# Sheet2.net
KiCad netlist of a schematic drawn in Altium Designer
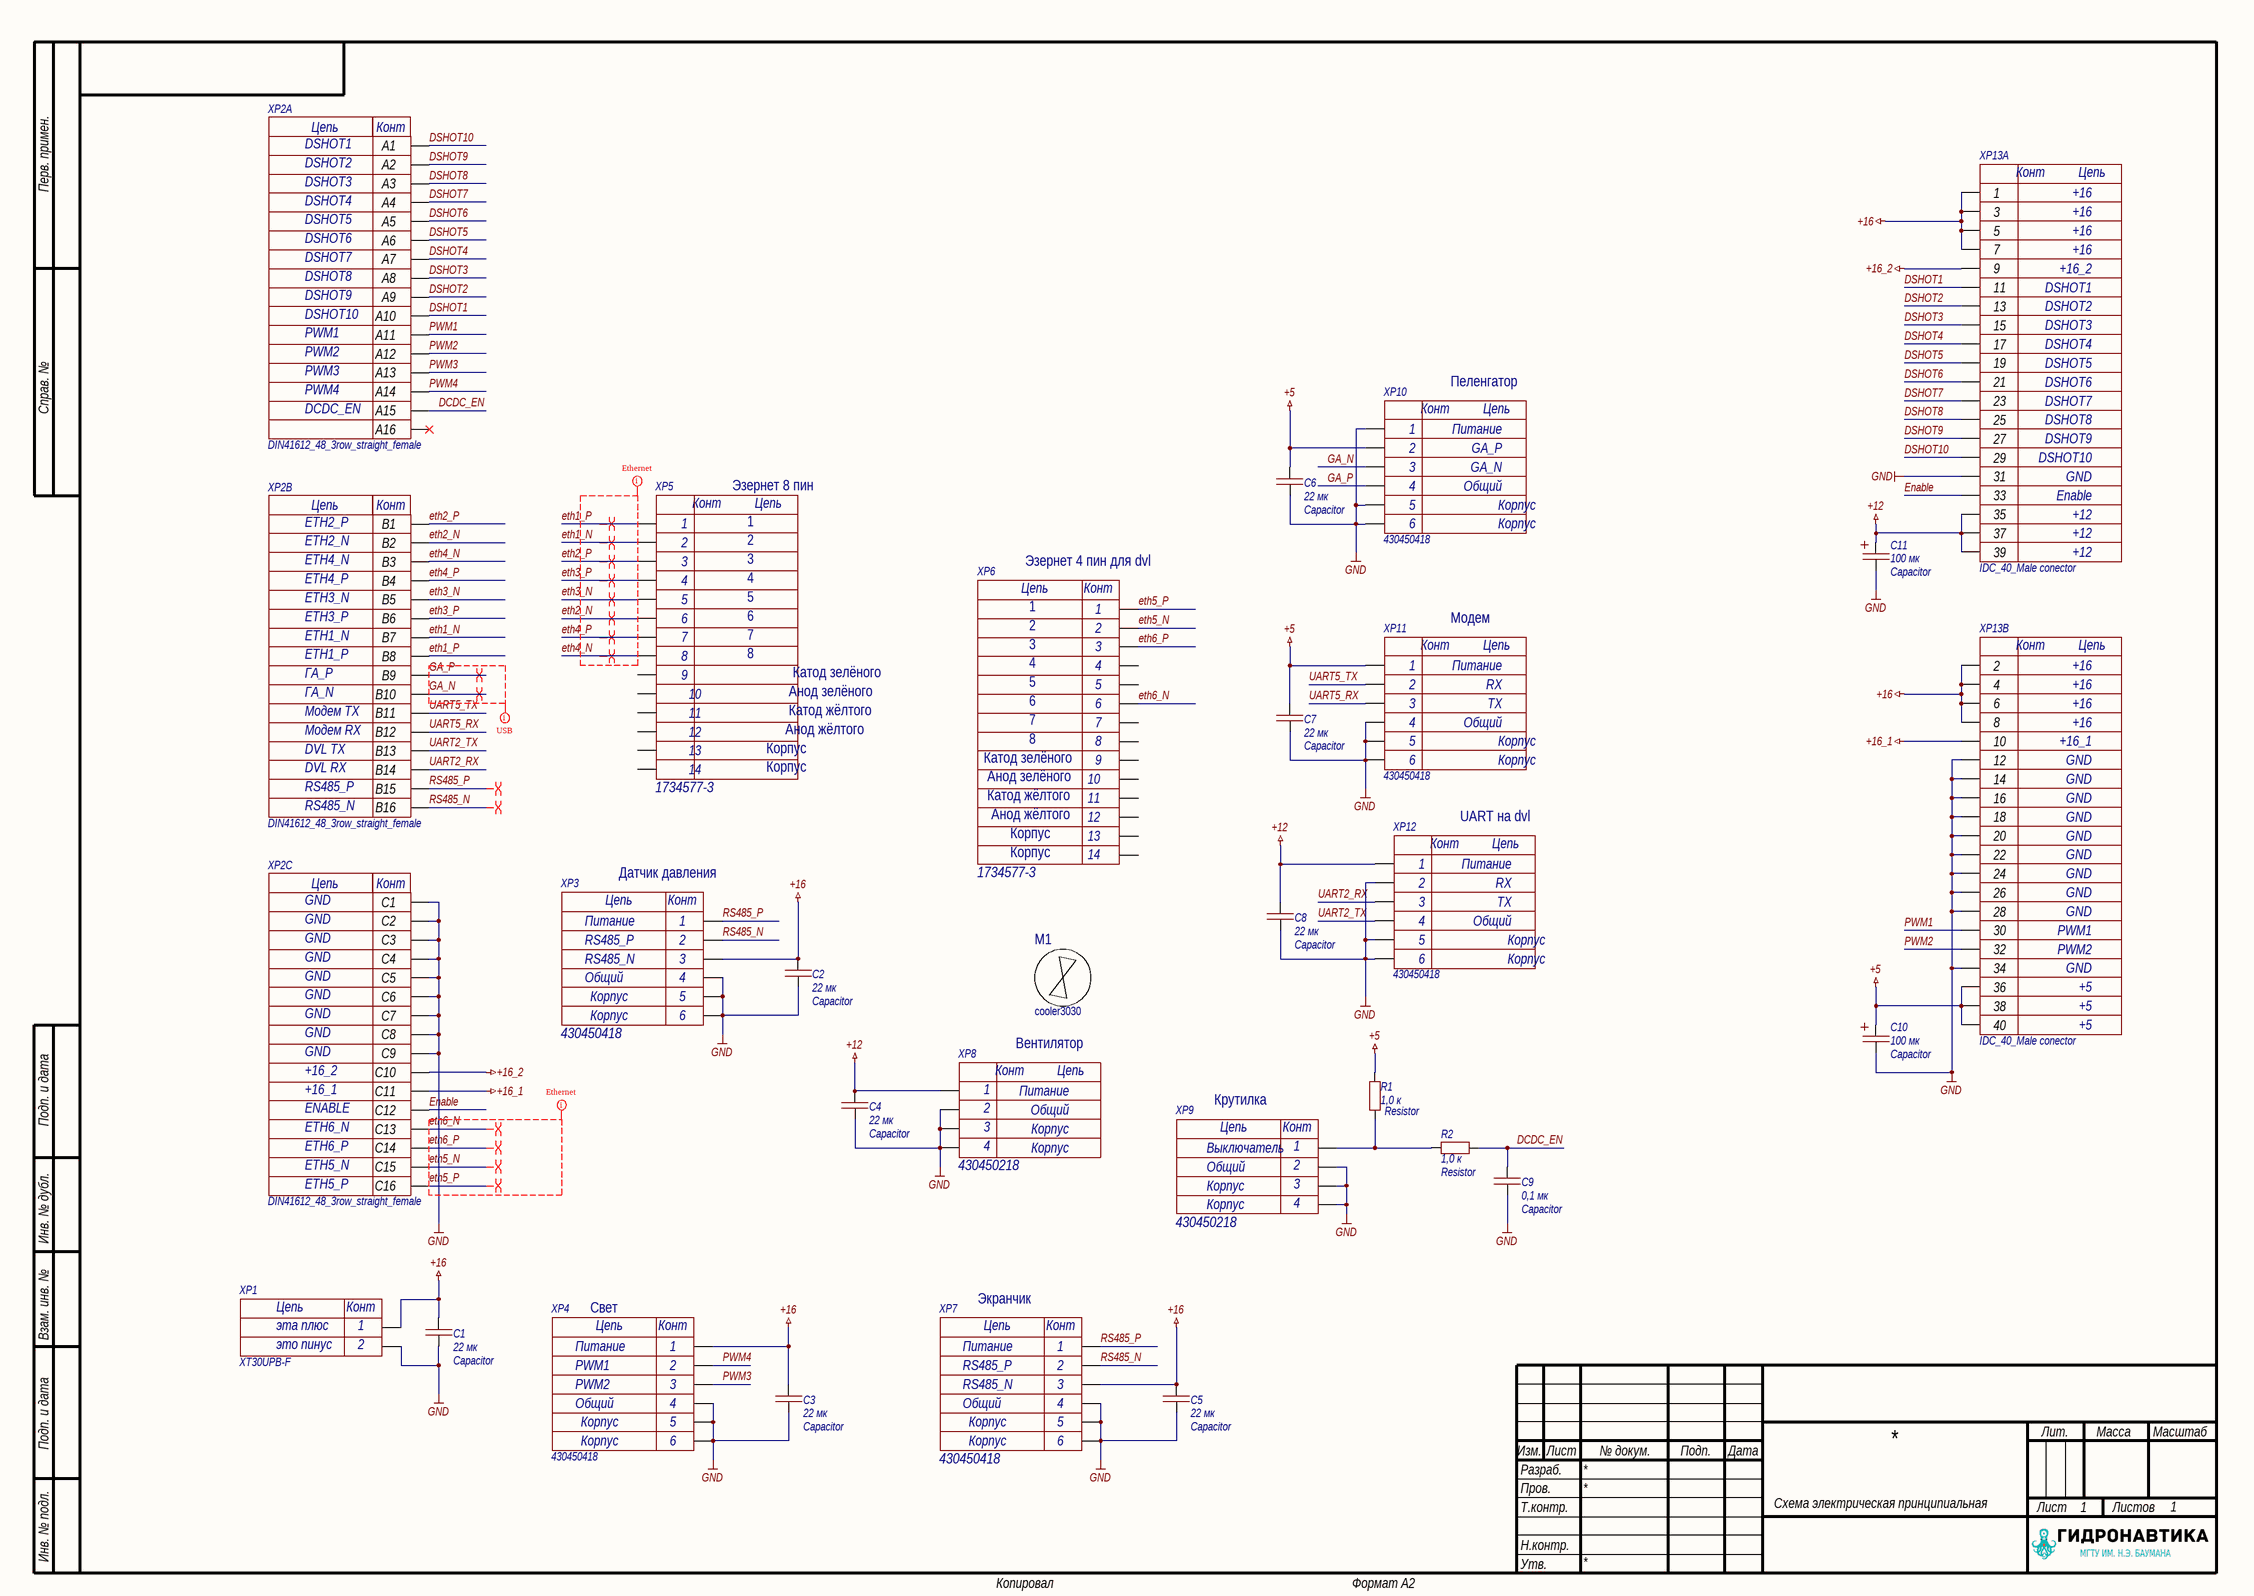
[diagram p0: Sheet2.SchDoc]

(export (version "E")
  (design (tool "Eeschema 10.0.6"))
  (components
    (comp (ref "C1")
      (value "Capacitor")
      (footprint "1210C")
      (description "Конденсатор 1210C ёмкостью 22 мк 10%, 25 В, X7R")
      (fields
        (field (name "ALTIUM_VALUE") "22 мк")
        (field (name "PART NUMBER") "Capacitor_22u_10_25V_X7R_1210C")
        (field (name "TOLERANCE") "10%")
      )
      (libsource (lib "Hydrolib") (part "Capacitor"))
    )
    (comp (ref "C2")
      (value "Capacitor")
      (footprint "1210C")
      (description "Конденсатор 1210C ёмкостью 22 мк 10%, 25 В, X7R")
      (fields
        (field (name "ALTIUM_VALUE") "22 мк")
        (field (name "PART NUMBER") "Capacitor_22u_10_25V_X7R_1210C")
        (field (name "TOLERANCE") "10%")
      )
      (libsource (lib "Hydrolib") (part "Capacitor"))
    )
    (comp (ref "C3")
      (value "Capacitor")
      (footprint "1210C")
      (description "Конденсатор 1210C ёмкостью 22 мк 10%, 25 В, X7R")
      (fields
        (field (name "ALTIUM_VALUE") "22 мк")
        (field (name "PART NUMBER") "Capacitor_22u_10_25V_X7R_1210C")
        (field (name "TOLERANCE") "10%")
      )
      (libsource (lib "Hydrolib") (part "Capacitor"))
    )
    (comp (ref "C4")
      (value "Capacitor")
      (footprint "1210C")
      (description "Конденсатор 1210C ёмкостью 22 мк 10%, 25 В, X7R")
      (fields
        (field (name "ALTIUM_VALUE") "22 мк")
        (field (name "PART NUMBER") "Capacitor_22u_10_25V_X7R_1210C")
        (field (name "TOLERANCE") "10%")
      )
      (libsource (lib "Hydrolib") (part "Capacitor"))
    )
    (comp (ref "C5")
      (value "Capacitor")
      (footprint "1210C")
      (description "Конденсатор 1210C ёмкостью 22 мк 10%, 25 В, X7R")
      (fields
        (field (name "ALTIUM_VALUE") "22 мк")
        (field (name "PART NUMBER") "Capacitor_22u_10_25V_X7R_1210C")
        (field (name "TOLERANCE") "10%")
      )
      (libsource (lib "Hydrolib") (part "Capacitor"))
    )
    (comp (ref "C6")
      (value "Capacitor")
      (footprint "1210C")
      (description "Конденсатор 1210C ёмкостью 22 мк 10%, 25 В, X7R")
      (fields
        (field (name "ALTIUM_VALUE") "22 мк")
        (field (name "PART NUMBER") "Capacitor_22u_10_25V_X7R_1210C")
        (field (name "TOLERANCE") "10%")
      )
      (libsource (lib "Hydrolib") (part "Capacitor"))
    )
    (comp (ref "C7")
      (value "Capacitor")
      (footprint "1210C")
      (description "Конденсатор 1210C ёмкостью 22 мк 10%, 25 В, X7R")
      (fields
        (field (name "ALTIUM_VALUE") "22 мк")
        (field (name "PART NUMBER") "Capacitor_22u_10_25V_X7R_1210C")
        (field (name "TOLERANCE") "10%")
      )
      (libsource (lib "Hydrolib") (part "Capacitor"))
    )
    (comp (ref "C8")
      (value "Capacitor")
      (footprint "1210C")
      (description "Конденсатор 1210C ёмкостью 22 мк 10%, 25 В, X7R")
      (fields
        (field (name "ALTIUM_VALUE") "22 мк")
        (field (name "PART NUMBER") "Capacitor_22u_10_25V_X7R_1210C")
        (field (name "TOLERANCE") "10%")
      )
      (libsource (lib "Hydrolib") (part "Capacitor"))
    )
    (comp (ref "C9")
      (value "Capacitor")
      (footprint "0603C")
      (description "Конденсатор 0603C ёмкостью 0,1 мк 10%, 50 В, X7R")
      (fields
        (field (name "ALTIUM_VALUE") "0,1 мк")
        (field (name "PART NUMBER") "Capacitor_0,1u_10_50V_X7R_0603C")
        (field (name "TOLERANCE") "10%")
      )
      (libsource (lib "Hydrolib") (part "Capacitor"))
    )
    (comp (ref "C10")
      (value "Capacitor")
      (footprint "ECAP_SMD_6,6x6,6")
      (description "Конденсатор алюминиевый электролитический 100мкФ 35В 20% SMD 6,6x6,6 мм")
      (fields
        (field (name "ALTIUM_VALUE") "100 мк")
        (field (name "PART NUMBER") "JCK1V101")
        (field (name "TOLERANCE") "20")
      )
      (libsource (lib "Hydrolib") (part "Capacitor_polar"))
    )
    (comp (ref "C11")
      (value "Capacitor")
      (footprint "ECAP_SMD_6,6x6,6")
      (description "Конденсатор алюминиевый электролитический 100мкФ 35В 20% SMD 6,6x6,6 мм")
      (fields
        (field (name "ALTIUM_VALUE") "100 мк")
        (field (name "PART NUMBER") "JCK1V101")
        (field (name "TOLERANCE") "20")
      )
      (libsource (lib "Hydrolib") (part "Capacitor_polar"))
    )
    (comp (ref "M1")
      (value "cooler3030")
      (footprint "cooler3030")
      (description "вентилятор 30*30 с дыркой на плате")
      (libsource (lib "Hydrolib") (part "cooler4040"))
    )
    (comp (ref "R1")
      (value "Resistor")
      (footprint "0603R")
      (description "Резистор номиналом 1,0 кОм 1%")
      (fields
        (field (name "ALTIUM_VALUE") "1,0 к")
        (field (name "PART NUMBER") "Resistor_1.0k_1_0603")
        (field (name "TOLERANCE") "1%")
      )
      (libsource (lib "") (part "Resistor_1"))
    )
    (comp (ref "R2")
      (value "Resistor")
      (footprint "0603R")
      (description "Резистор номиналом 1,0 кОм 1%")
      (fields
        (field (name "ALTIUM_VALUE") "1,0 к")
        (field (name "PART NUMBER") "Resistor_1.0k_1_0603")
        (field (name "TOLERANCE") "1%")
      )
      (libsource (lib "Hydrolib") (part "Resistor"))
    )
    (comp (ref "XP1")
      (value "XT30UPB-F")
      (footprint "XT30UPB-F")
      (description "30 А (15 продолжительно), прямая мать")
      (fields (field (name "VALUE2") "это пинус") (field (name "VALUE1") "эта плюс"))
      (libsource (lib "Hydrolib") (part "Polar_Conn"))
    )
    (comp (ref "XP2")
      (value "DIN41612_48_3row_straight_female")
      (footprint "DIN41612_48_3row_straight_female")
      (fields
        (field (name "PARAMETER 14") "DCDC_EN")
        (field (name "PARAMETER 16") "RS485_N")
        (field (name "PARAMETER 15") "PWM4")
        (field (name "PARAMETER 12") "DSHOT7")
        (field (name "PARAMETER 13") "DSHOT5")
        (field (name "PARAMETER 11") "DSHOT6")
        (field (name "PARAMETER 10") "DSHOT4")
        (field (name "PARAMETER 9") "DSHOT3")
        (field (name "PARAMETER 8") "DSHOT2")
        (field (name "PARAMETER 5") "DSHOT1")
        (field (name "PARAMETER 6") "PWM2")
        (field (name "PARAMETER 7") "PWM3")
        (field (name "PARAMETER 4") "DSHOT10")
        (field (name "PARAMETER 3") "DSHOT9")
        (field (name "PARAMETER 2") "DSHOT8")
        (field (name "PARAMETER 1") "PWM1")
      )
      (libsource (lib "") (part "Conn_48pin_3row_1"))
    )
    (comp (ref "XP3")
      (value "430450418")
      (footprint "MOLEX_430450418")
      (description "Разъем типа провод-плата, 3 мм, 4 контакт(-ов), Штыревой Разъем, для поверностного монтажа")
      (fields
        (field (name "VALUE1") "Питание")
        (field (name "VALUE2") "RS485_P")
        (field (name "VALUE3") "RS485_N")
        (field (name "VALUE4") "Общий")
        (field (name "PART NUMBER") "Molex_430450418")
      )
      (libsource (lib "") (part "Molex_430450415_1"))
    )
    (comp (ref "XP4")
      (value "430450418")
      (footprint "MOLEX_430450418")
      (description "Разъем типа провод-плата, 3 мм, 4 контакт(-ов), Штыревой Разъем, для поверностного монтажа")
      (fields
        (field (name "VALUE1") "Питание")
        (field (name "VALUE2") "PWM1")
        (field (name "VALUE3") "PWM2")
        (field (name "VALUE4") "Общий")
        (field (name "PART NUMBER") "Molex_430450418")
      )
      (libsource (lib "") (part "Molex_430450415_1"))
    )
    (comp (ref "XP5")
      (value "1734577-3")
      (footprint "1-1734577-3-rj45-8p8c")
      (description "Модульный разъем, Cat3, RJ45, Гнездо, 8 контакт(-ов), 8 вывод(-ов), 1 порт(-ов)")
      (fields (field (name "PART NUMBER") "1-1734577-3-rj45-8p8c"))
      (libsource (lib "Hydrolib") (part "1-1734577-3-rj45-8p8c"))
    )
    (comp (ref "XP6")
      (value "1734577-3")
      (footprint "1-1734577-3-rj45-8p8c")
      (description "Модульный разъем, Cat3, RJ45, Гнездо, 8 контакт(-ов), 8 вывод(-ов), 1 порт(-ов)")
      (fields (field (name "PART NUMBER") "1-1734577-3-rj45-8p8c"))
      (libsource (lib "") (part "1-1734577-3-rj45-8p8c_1"))
    )
    (comp (ref "XP7")
      (value "430450418")
      (footprint "MOLEX_430450418")
      (description "Разъем типа провод-плата, 3 мм, 4 контакт(-ов), Штыревой Разъем, для поверностного монтажа")
      (fields
        (field (name "VALUE1") "Питание")
        (field (name "VALUE2") "RS485_P")
        (field (name "VALUE3") "RS485_N")
        (field (name "VALUE4") "Общий")
        (field (name "PART NUMBER") "Molex_430450418")
      )
      (libsource (lib "") (part "Molex_430450415_1"))
    )
    (comp (ref "XP8")
      (value "430450218")
      (footprint "Molex_430450218")
      (fields
        (field (name "VALUE3") "Корпус")
        (field (name "VALUE2") "Общий")
        (field (name "VALUE4") "Корпус")
        (field (name "VALUE1") "Питание")
        (field (name "PART NUMBER") "Molex_430450218")
      )
      (libsource (lib "Hydrolib") (part "Molex_430450218"))
    )
    (comp (ref "XP9")
      (value "430450218")
      (footprint "Molex_430450218")
      (fields
        (field (name "VALUE3") "Корпус")
        (field (name "VALUE2") "Общий")
        (field (name "VALUE4") "Корпус")
        (field (name "VALUE1") "Выключатель")
        (field (name "PART NUMBER") "Molex_430450218")
      )
      (libsource (lib "Hydrolib") (part "Molex_430450218"))
    )
    (comp (ref "XP10")
      (value "430450418")
      (footprint "MOLEX_430450418")
      (description "Разъем типа провод-плата, 3 мм, 4 контакт(-ов), Штыревой Разъем, для поверностного монтажа")
      (fields
        (field (name "VALUE1") "Питание")
        (field (name "VALUE2") "GA_P")
        (field (name "VALUE3") "GA_N")
        (field (name "VALUE4") "Общий")
        (field (name "PART NUMBER") "Molex_430450418")
      )
      (libsource (lib "Hydrolib") (part "Molex_430450415"))
    )
    (comp (ref "XP11")
      (value "430450418")
      (footprint "MOLEX_430450418")
      (description "Разъем типа провод-плата, 3 мм, 4 контакт(-ов), Штыревой Разъем, для поверностного монтажа")
      (fields
        (field (name "VALUE1") "Питание")
        (field (name "VALUE2") "RX")
        (field (name "VALUE3") "TX")
        (field (name "VALUE4") "Общий")
        (field (name "PART NUMBER") "Molex_430450418")
      )
      (libsource (lib "Hydrolib") (part "Molex_430450415"))
    )
    (comp (ref "XP12")
      (value "430450418")
      (footprint "MOLEX_430450418")
      (description "Разъем типа провод-плата, 3 мм, 4 контакт(-ов), Штыревой Разъем, для поверностного монтажа")
      (fields
        (field (name "VALUE1") "Питание")
        (field (name "VALUE2") "RX")
        (field (name "VALUE3") "TX")
        (field (name "VALUE4") "Общий")
        (field (name "PART NUMBER") "Molex_430450418")
      )
      (libsource (lib "Hydrolib") (part "Molex_430450415"))
    )
    (comp (ref "XP13")
      (value "IDC_40_Male conector")
      (footprint "IDC_40_Male conector")
      (description "IDC 40-пиновый разъём прямая вилка")
      (fields
        (field (name "VALUE17") "GND")
        (field (name "VALUE20") "+5")
        (field (name "VALUE19") "+5")
        (field (name "VALUE18") "+5")
        (field (name "VALUE16") "PWM2")
        (field (name "VALUE15") "PWM1")
        (field (name "VALUE14") "GND")
        (field (name "VALUE13") "GND")
        (field (name "VALUE12") "GND")
        (field (name "VALUE11") "GND")
        (field (name "VALUE10") "GND")
        (field (name "VALUE9") "GND")
        (field (name "VALUE8") "GND")
        (field (name "VALUE7") "GND")
        (field (name "VALUE6") "GND")
        (field (name "VALUE5") "+16_1")
        (field (name "VALUE4") "+16")
        (field (name "VALUE3") "+16")
        (field (name "VALUE2") "+16")
        (field (name "VALUE1") "+16")
      )
      (libsource (lib "Hydrolib") (part "Conn_40pin_double"))
    )
  )
  (nets
    (net (code "1") (name "+5") (class "Default")
      (node (ref "C10") (pin "1") (pinfunction "1_1") (pintype "passive"))
      (node (ref "C6") (pin "2") (pinfunction "2_2") (pintype "passive"))
      (node (ref "C7") (pin "2") (pinfunction "2_2") (pintype "passive"))
      (node (ref "R1") (pin "1") (pinfunction "1_1") (pintype "passive"))
      (node (ref "XP10") (pin "2") (pinfunction "2_2") (pintype "passive"))
      (node (ref "XP11") (pin "1") (pinfunction "1_1") (pintype "passive"))
      (node (ref "XP13") (pin "36") (pinfunction "36_36") (pintype "passive"))
      (node (ref "XP13") (pin "38") (pinfunction "38_38") (pintype "passive"))
      (node (ref "XP13") (pin "40") (pinfunction "40_40") (pintype "passive"))
    )
    (net (code "2") (name "+12") (class "Default")
      (node (ref "C11") (pin "1") (pinfunction "1_1") (pintype "passive"))
      (node (ref "C4") (pin "2") (pinfunction "2_2") (pintype "passive"))
      (node (ref "C8") (pin "2") (pinfunction "2_2") (pintype "passive"))
      (node (ref "XP12") (pin "1") (pinfunction "1_1") (pintype "passive"))
      (node (ref "XP13") (pin "35") (pinfunction "35_35") (pintype "passive"))
      (node (ref "XP13") (pin "37") (pinfunction "37_37") (pintype "passive"))
      (node (ref "XP13") (pin "39") (pinfunction "39_39") (pintype "passive"))
      (node (ref "XP8") (pin "1") (pinfunction "1_1") (pintype "passive"))
    )
    (net (code "3") (name "+16") (class "Default")
      (node (ref "C1") (pin "2") (pinfunction "2_2") (pintype "passive"))
      (node (ref "C2") (pin "2") (pinfunction "2_2") (pintype "passive"))
      (node (ref "C3") (pin "2") (pinfunction "2_2") (pintype "passive"))
      (node (ref "C5") (pin "2") (pinfunction "2_2") (pintype "passive"))
      (node (ref "XP1") (pin "P") (pinfunction "P_P") (pintype "passive"))
      (node (ref "XP13") (pin "1") (pinfunction "1_1") (pintype "passive"))
      (node (ref "XP13") (pin "2") (pinfunction "2_2") (pintype "passive"))
      (node (ref "XP13") (pin "3") (pinfunction "3_3") (pintype "passive"))
      (node (ref "XP13") (pin "4") (pinfunction "4_4") (pintype "passive"))
      (node (ref "XP13") (pin "5") (pinfunction "5_5") (pintype "passive"))
      (node (ref "XP13") (pin "6") (pinfunction "6_6") (pintype "passive"))
      (node (ref "XP13") (pin "7") (pinfunction "7_7") (pintype "passive"))
      (node (ref "XP13") (pin "8") (pinfunction "8_8") (pintype "passive"))
      (node (ref "XP3") (pin "3") (pinfunction "3_3") (pintype "passive"))
      (node (ref "XP4") (pin "1") (pinfunction "1_1") (pintype "passive"))
      (node (ref "XP7") (pin "3") (pinfunction "3_3") (pintype "passive"))
    )
    (net (code "4") (name "+16_1") (class "Default")
      (node (ref "XP13") (pin "10") (pinfunction "10_10") (pintype "passive"))
      (node (ref "XP2") (pin "C11") (pinfunction "C11_C11") (pintype "passive"))
    )
    (net (code "5") (name "+16_2") (class "Default")
      (node (ref "XP13") (pin "9") (pinfunction "9_9") (pintype "passive"))
      (node (ref "XP2") (pin "C10") (pinfunction "C10_C10") (pintype "passive"))
    )
    (net (code "6") (name "/DCDC_EN") (class "Default")
      (node (ref "C9") (pin "2") (pinfunction "2_2") (pintype "passive"))
      (node (ref "R2") (pin "1") (pinfunction "1_1") (pintype "passive"))
      (node (ref "XP2") (pin "A15") (pinfunction "A15_A15") (pintype "passive"))
    )
    (net (code "7") (name "/DSHOT1") (class "Default")
      (node (ref "XP13") (pin "11") (pinfunction "11_11") (pintype "passive"))
      (node (ref "XP2") (pin "A10") (pinfunction "A10_A10") (pintype "passive"))
    )
    (net (code "8") (name "/DSHOT2") (class "Default")
      (node (ref "XP13") (pin "13") (pinfunction "13_13") (pintype "passive"))
      (node (ref "XP2") (pin "A9") (pinfunction "A9_A9") (pintype "passive"))
    )
    (net (code "9") (name "/DSHOT3") (class "Default")
      (node (ref "XP13") (pin "15") (pinfunction "15_15") (pintype "passive"))
      (node (ref "XP2") (pin "A8") (pinfunction "A8_A8") (pintype "passive"))
    )
    (net (code "10") (name "/DSHOT4") (class "Default")
      (node (ref "XP13") (pin "17") (pinfunction "17_17") (pintype "passive"))
      (node (ref "XP2") (pin "A7") (pinfunction "A7_A7") (pintype "passive"))
    )
    (net (code "11") (name "/DSHOT5") (class "Default")
      (node (ref "XP13") (pin "19") (pinfunction "19_19") (pintype "passive"))
      (node (ref "XP2") (pin "A6") (pinfunction "A6_A6") (pintype "passive"))
    )
    (net (code "12") (name "/DSHOT6") (class "Default")
      (node (ref "XP13") (pin "21") (pinfunction "21_21") (pintype "passive"))
      (node (ref "XP2") (pin "A5") (pinfunction "A5_A5") (pintype "passive"))
    )
    (net (code "13") (name "/DSHOT7") (class "Default")
      (node (ref "XP13") (pin "23") (pinfunction "23_23") (pintype "passive"))
      (node (ref "XP2") (pin "A4") (pinfunction "A4_A4") (pintype "passive"))
    )
    (net (code "14") (name "/DSHOT8") (class "Default")
      (node (ref "XP13") (pin "25") (pinfunction "25_25") (pintype "passive"))
      (node (ref "XP2") (pin "A3") (pinfunction "A3_A3") (pintype "passive"))
    )
    (net (code "15") (name "/DSHOT9") (class "Default")
      (node (ref "XP13") (pin "27") (pinfunction "27_27") (pintype "passive"))
      (node (ref "XP2") (pin "A2") (pinfunction "A2_A2") (pintype "passive"))
    )
    (net (code "16") (name "/DSHOT10") (class "Default")
      (node (ref "XP13") (pin "29") (pinfunction "29_29") (pintype "passive"))
      (node (ref "XP2") (pin "A1") (pinfunction "A1_A1") (pintype "passive"))
    )
    (net (code "17") (name "/Enable") (class "Default")
      (node (ref "XP13") (pin "33") (pinfunction "33_33") (pintype "passive"))
      (node (ref "XP2") (pin "C12") (pinfunction "C12_C12") (pintype "passive"))
    )
    (net (code "18") (name "/GA_N") (class "Default")
      (node (ref "XP10") (pin "3") (pinfunction "3_3") (pintype "passive"))
      (node (ref "XP2") (pin "B10") (pinfunction "B10_B10") (pintype "passive"))
    )
    (net (code "19") (name "/GA_P") (class "Default")
      (node (ref "XP10") (pin "4") (pinfunction "4_4") (pintype "passive"))
      (node (ref "XP2") (pin "B9") (pinfunction "B9_B9") (pintype "passive"))
    )
    (net (code "20") (name "/PWM1") (class "Default")
      (node (ref "XP13") (pin "30") (pinfunction "30_30") (pintype "passive"))
      (node (ref "XP2") (pin "A11") (pinfunction "A11_A11") (pintype "passive"))
    )
    (net (code "21") (name "/PWM2") (class "Default")
      (node (ref "XP13") (pin "32") (pinfunction "32_32") (pintype "passive"))
      (node (ref "XP2") (pin "A12") (pinfunction "A12_A12") (pintype "passive"))
    )
    (net (code "22") (name "/PWM3") (class "Default")
      (node (ref "XP2") (pin "A13") (pinfunction "A13_A13") (pintype "passive"))
      (node (ref "XP4") (pin "3") (pinfunction "3_3") (pintype "passive"))
    )
    (net (code "23") (name "/PWM4") (class "Default")
      (node (ref "XP2") (pin "A14") (pinfunction "A14_A14") (pintype "passive"))
      (node (ref "XP4") (pin "2") (pinfunction "2_2") (pintype "passive"))
    )
    (net (code "24") (name "/RS485_N") (class "Default")
      (node (ref "XP2") (pin "B16") (pinfunction "B16_B16") (pintype "passive"))
      (node (ref "XP3") (pin "2") (pinfunction "2_2") (pintype "passive"))
      (node (ref "XP7") (pin "2") (pinfunction "2_2") (pintype "passive"))
    )
    (net (code "25") (name "/RS485_P") (class "Default")
      (node (ref "XP2") (pin "B15") (pinfunction "B15_B15") (pintype "passive"))
      (node (ref "XP3") (pin "1") (pinfunction "1_1") (pintype "passive"))
      (node (ref "XP7") (pin "1") (pinfunction "1_1") (pintype "passive"))
    )
    (net (code "26") (name "/UART2_RX") (class "Default")
      (node (ref "XP12") (pin "3") (pinfunction "3_3") (pintype "passive"))
      (node (ref "XP2") (pin "B14") (pinfunction "B14_B14") (pintype "passive"))
    )
    (net (code "27") (name "/UART2_TX") (class "Default")
      (node (ref "XP12") (pin "4") (pinfunction "4_4") (pintype "passive"))
      (node (ref "XP2") (pin "B13") (pinfunction "B13_B13") (pintype "passive"))
    )
    (net (code "28") (name "/UART5_RX") (class "Default")
      (node (ref "XP11") (pin "3") (pinfunction "3_3") (pintype "passive"))
      (node (ref "XP2") (pin "B12") (pinfunction "B12_B12") (pintype "passive"))
    )
    (net (code "29") (name "/UART5_TX") (class "Default")
      (node (ref "XP11") (pin "2") (pinfunction "2_2") (pintype "passive"))
      (node (ref "XP2") (pin "B11") (pinfunction "B11_B11") (pintype "passive"))
    )
    (net (code "30") (name "/eth1_N") (class "Default")
      (node (ref "XP2") (pin "B7") (pinfunction "B7_B7") (pintype "passive"))
      (node (ref "XP5") (pin "2") (pinfunction "2_2") (pintype "passive"))
    )
    (net (code "31") (name "/eth1_P") (class "Default")
      (node (ref "XP2") (pin "B8") (pinfunction "B8_B8") (pintype "passive"))
      (node (ref "XP5") (pin "1") (pinfunction "1_1") (pintype "passive"))
    )
    (net (code "32") (name "/eth2_N") (class "Default")
      (node (ref "XP2") (pin "B2") (pinfunction "B2_B2") (pintype "passive"))
      (node (ref "XP5") (pin "6") (pinfunction "6_6") (pintype "passive"))
    )
    (net (code "33") (name "/eth2_P") (class "Default")
      (node (ref "XP2") (pin "B1") (pinfunction "B1_B1") (pintype "passive"))
      (node (ref "XP5") (pin "3") (pinfunction "3_3") (pintype "passive"))
    )
    (net (code "34") (name "/eth3_N") (class "Default")
      (node (ref "XP2") (pin "B5") (pinfunction "B5_B5") (pintype "passive"))
      (node (ref "XP5") (pin "5") (pinfunction "5_5") (pintype "passive"))
    )
    (net (code "35") (name "/eth3_P") (class "Default")
      (node (ref "XP2") (pin "B6") (pinfunction "B6_B6") (pintype "passive"))
      (node (ref "XP5") (pin "4") (pinfunction "4_4") (pintype "passive"))
    )
    (net (code "36") (name "/eth4_N") (class "Default")
      (node (ref "XP2") (pin "B3") (pinfunction "B3_B3") (pintype "passive"))
      (node (ref "XP5") (pin "8") (pinfunction "8_8") (pintype "passive"))
    )
    (net (code "37") (name "/eth4_P") (class "Default")
      (node (ref "XP2") (pin "B4") (pinfunction "B4_B4") (pintype "passive"))
      (node (ref "XP5") (pin "7") (pinfunction "7_7") (pintype "passive"))
    )
    (net (code "38") (name "/eth5_N") (class "Default")
      (node (ref "XP2") (pin "C15") (pinfunction "C15_C15") (pintype "passive"))
      (node (ref "XP6") (pin "2") (pinfunction "2_2") (pintype "passive"))
    )
    (net (code "39") (name "/eth5_P") (class "Default")
      (node (ref "XP2") (pin "C16") (pinfunction "C16_C16") (pintype "passive"))
      (node (ref "XP6") (pin "1") (pinfunction "1_1") (pintype "passive"))
    )
    (net (code "40") (name "/eth6_N") (class "Default")
      (node (ref "XP2") (pin "C13") (pinfunction "C13_C13") (pintype "passive"))
      (node (ref "XP6") (pin "6") (pinfunction "6_6") (pintype "passive"))
    )
    (net (code "41") (name "/eth6_P") (class "Default")
      (node (ref "XP2") (pin "C14") (pinfunction "C14_C14") (pintype "passive"))
      (node (ref "XP6") (pin "3") (pinfunction "3_3") (pintype "passive"))
    )
    (net (code "42") (name "GND") (class "Default")
      (node (ref "C1") (pin "1") (pinfunction "1_1") (pintype "passive"))
      (node (ref "C10") (pin "2") (pinfunction "2_2") (pintype "passive"))
      (node (ref "C11") (pin "2") (pinfunction "2_2") (pintype "passive"))
      (node (ref "C2") (pin "1") (pinfunction "1_1") (pintype "passive"))
      (node (ref "C3") (pin "1") (pinfunction "1_1") (pintype "passive"))
      (node (ref "C4") (pin "1") (pinfunction "1_1") (pintype "passive"))
      (node (ref "C5") (pin "1") (pinfunction "1_1") (pintype "passive"))
      (node (ref "C6") (pin "1") (pinfunction "1_1") (pintype "passive"))
      (node (ref "C7") (pin "1") (pinfunction "1_1") (pintype "passive"))
      (node (ref "C8") (pin "1") (pinfunction "1_1") (pintype "passive"))
      (node (ref "C9") (pin "1") (pinfunction "1_1") (pintype "passive"))
      (node (ref "XP1") (pin "N") (pinfunction "N_N") (pintype "passive"))
      (node (ref "XP10") (pin "0") (pinfunction "0_0") (pintype "passive"))
      (node (ref "XP10") (pin "1") (pinfunction "1_1") (pintype "passive"))
      (node (ref "XP11") (pin "0") (pinfunction "0_0") (pintype "passive"))
      (node (ref "XP11") (pin "4") (pinfunction "4_4") (pintype "passive"))
      (node (ref "XP12") (pin "0") (pinfunction "0_0") (pintype "passive"))
      (node (ref "XP12") (pin "2") (pinfunction "2_2") (pintype "passive"))
      (node (ref "XP13") (pin "12") (pinfunction "12_12") (pintype "passive"))
      (node (ref "XP13") (pin "14") (pinfunction "14_14") (pintype "passive"))
      (node (ref "XP13") (pin "16") (pinfunction "16_16") (pintype "passive"))
      (node (ref "XP13") (pin "18") (pinfunction "18_18") (pintype "passive"))
      (node (ref "XP13") (pin "20") (pinfunction "20_20") (pintype "passive"))
      (node (ref "XP13") (pin "22") (pinfunction "22_22") (pintype "passive"))
      (node (ref "XP13") (pin "24") (pinfunction "24_24") (pintype "passive"))
      (node (ref "XP13") (pin "26") (pinfunction "26_26") (pintype "passive"))
      (node (ref "XP13") (pin "28") (pinfunction "28_28") (pintype "passive"))
      (node (ref "XP13") (pin "31") (pinfunction "31_31") (pintype "passive"))
      (node (ref "XP13") (pin "34") (pinfunction "34_34") (pintype "passive"))
      (node (ref "XP2") (pin "C1") (pinfunction "C1_C1") (pintype "passive"))
      (node (ref "XP2") (pin "C2") (pinfunction "C2_C2") (pintype "passive"))
      (node (ref "XP2") (pin "C3") (pinfunction "C3_C3") (pintype "passive"))
      (node (ref "XP2") (pin "C4") (pinfunction "C4_C4") (pintype "passive"))
      (node (ref "XP2") (pin "C5") (pinfunction "C5_C5") (pintype "passive"))
      (node (ref "XP2") (pin "C6") (pinfunction "C6_C6") (pintype "passive"))
      (node (ref "XP2") (pin "C7") (pinfunction "C7_C7") (pintype "passive"))
      (node (ref "XP2") (pin "C8") (pinfunction "C8_C8") (pintype "passive"))
      (node (ref "XP2") (pin "C9") (pinfunction "C9_C9") (pintype "passive"))
      (node (ref "XP3") (pin "0") (pinfunction "0_0") (pintype "passive"))
      (node (ref "XP3") (pin "4") (pinfunction "4_4") (pintype "passive"))
      (node (ref "XP4") (pin "0") (pinfunction "0_0") (pintype "passive"))
      (node (ref "XP4") (pin "4") (pinfunction "4_4") (pintype "passive"))
      (node (ref "XP7") (pin "0") (pinfunction "0_0") (pintype "passive"))
      (node (ref "XP7") (pin "4") (pinfunction "4_4") (pintype "passive"))
      (node (ref "XP8") (pin "0") (pinfunction "0_0") (pintype "passive"))
      (node (ref "XP8") (pin "2") (pinfunction "2_2") (pintype "passive"))
      (node (ref "XP9") (pin "0") (pinfunction "0_0") (pintype "passive"))
      (node (ref "XP9") (pin "2") (pinfunction "2_2") (pintype "passive"))
    )
    (net (code "43") (name "Net-(R1-Pad2)") (class "Default")
      (node (ref "R1") (pin "2") (pinfunction "2_2") (pintype "passive"))
      (node (ref "R2") (pin "2") (pinfunction "2_2") (pintype "passive"))
      (node (ref "XP9") (pin "1") (pinfunction "1_1") (pintype "passive"))
    )
    (net (code "44") (name "unconnected-(XP2-PadA16)") (class "Default")
      (node (ref "XP2") (pin "A16") (pinfunction "A16_A16") (pintype "passive+no_connect"))
    )
    (net (code "45") (name "unconnected-(XP5-Pad9)") (class "Default")
      (node (ref "XP5") (pin "9") (pinfunction "9_9") (pintype "passive"))
    )
    (net (code "46") (name "unconnected-(XP5-Pad10)") (class "Default")
      (node (ref "XP5") (pin "10") (pinfunction "10_10") (pintype "passive"))
    )
    (net (code "47") (name "unconnected-(XP5-Pad11)") (class "Default")
      (node (ref "XP5") (pin "11") (pinfunction "11_11") (pintype "passive"))
    )
    (net (code "48") (name "unconnected-(XP5-Pad12)") (class "Default")
      (node (ref "XP5") (pin "12") (pinfunction "12_12") (pintype "passive"))
    )
    (net (code "49") (name "unconnected-(XP5-PadMH1)") (class "Default")
      (node (ref "XP5") (pin "MH1") (pinfunction "MH1_MH1") (pintype "passive"))
    )
    (net (code "50") (name "unconnected-(XP5-PadMH2)") (class "Default")
      (node (ref "XP5") (pin "MH2") (pinfunction "MH2_MH2") (pintype "passive"))
    )
    (net (code "51") (name "unconnected-(XP6-Pad4)") (class "Default")
      (node (ref "XP6") (pin "4") (pinfunction "4_4") (pintype "passive"))
    )
    (net (code "52") (name "unconnected-(XP6-Pad5)") (class "Default")
      (node (ref "XP6") (pin "5") (pinfunction "5_5") (pintype "passive"))
    )
    (net (code "53") (name "unconnected-(XP6-Pad7)") (class "Default")
      (node (ref "XP6") (pin "7") (pinfunction "7_7") (pintype "passive"))
    )
    (net (code "54") (name "unconnected-(XP6-Pad8)") (class "Default")
      (node (ref "XP6") (pin "8") (pinfunction "8_8") (pintype "passive"))
    )
    (net (code "55") (name "unconnected-(XP6-Pad9)") (class "Default")
      (node (ref "XP6") (pin "9") (pinfunction "9_9") (pintype "passive"))
    )
    (net (code "56") (name "unconnected-(XP6-Pad10)") (class "Default")
      (node (ref "XP6") (pin "10") (pinfunction "10_10") (pintype "passive"))
    )
    (net (code "57") (name "unconnected-(XP6-Pad11)") (class "Default")
      (node (ref "XP6") (pin "11") (pinfunction "11_11") (pintype "passive"))
    )
    (net (code "58") (name "unconnected-(XP6-Pad12)") (class "Default")
      (node (ref "XP6") (pin "12") (pinfunction "12_12") (pintype "passive"))
    )
    (net (code "59") (name "unconnected-(XP6-PadMH1)") (class "Default")
      (node (ref "XP6") (pin "MH1") (pinfunction "MH1_MH1") (pintype "passive"))
    )
    (net (code "60") (name "unconnected-(XP6-PadMH2)") (class "Default")
      (node (ref "XP6") (pin "MH2") (pinfunction "MH2_MH2") (pintype "passive"))
    )
  )
)
